# ProstheticController.net
KiCad netlist of a schematic drawn in Altium Designer
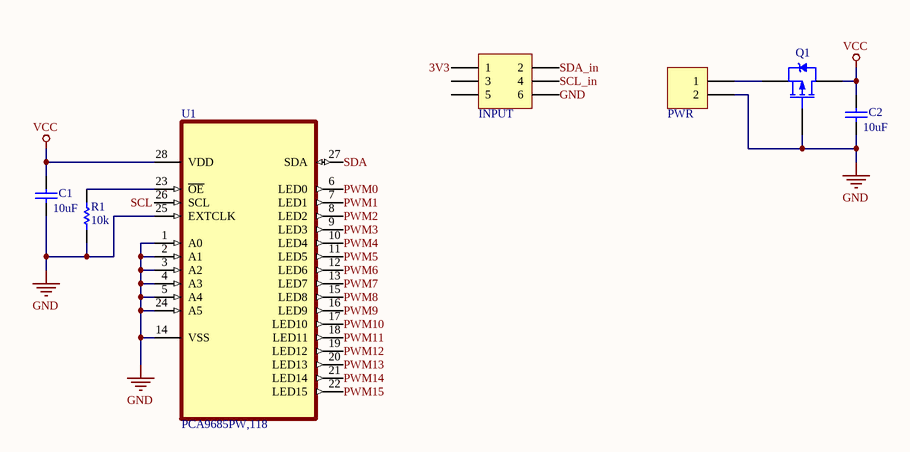
[diagram p0: ProstheticController.SchDoc]

(export (version "E")
  (design (tool "Eeschema 10.0.6"))
  (components
    (comp (ref "C1")
      (value "10uF")
      (footprint "0805")
      (description ".1, 10%, 50V")
      (fields (field (name "GFUPARTNO") "CL21A475KPFNNNE"))
      (libsource (lib "AltiumGFU64") (part "Cap"))
    )
    (comp (ref "C2")
      (value "10uF")
      (footprint "0805")
      (description ".1, 10%, 50V")
      (fields (field (name "GFUPARTNO") "CL21A475KPFNNNE"))
      (libsource (lib "AltiumGFU64") (part "Cap"))
    )
    (comp (ref "INPUT")
      (value "90131-0123")
      (footprint "HDR2X3")
      (description "MOLEX CONN HEADER 6POS 2ROW .100\" STR TIN")
      (libsource (lib "AltiumGFU64") (part "Header 3X2"))
    )
    (comp (ref "PWR")
      (value "90120-0122")
      (footprint "HDR1X2")
      (description "MOLEX CONN HEADER 2POS .100\" STR TIN")
      (libsource (lib "AltiumGFU64") (part "Header 2"))
    )
    (comp (ref "Q1")
      (value "FQP27P06")
      (footprint "TO-220")
      (description "MOSFET P-CH 60V 27A TO-220")
      (libsource (lib "AltiumGFU64") (part "MOSFET-P-ALT"))
    )
    (comp (ref "R1")
      (value "10k")
      (footprint "0805_RES_HD")
      (description "RES 10K OHM 1/8W 5% 0805")
      (fields (field (name "GFUPARTNO") "RC2012F752CS"))
      (libsource (lib "AltiumGFU64") (part "ResBasic"))
    )
    (comp (ref "U1")
      (value "PCA9685PW,118")
      (footprint "SnapEDApcb:SOP65P640X110-28N")
      (description "LED Driver IC 16 Output Linear PWM Dimming 25mA 28-TSSOP")
      (fields (field (name "DIGI-KEY_PART_NUMBER") "568-11925-1-ND") (field (name "MF") "NXP USA"))
      (libsource (lib "SERVO_DRIVER") (part "PCA9685PW,118"))
    )
  )
  (nets
    (net (code "1") (name "/3V3") (class "Default")
      (node (ref "INPUT") (pin "1") (pinfunction "1_1") (pintype "passive"))
    )
    (net (code "2") (name "/PWM0") (class "Default")
      (node (ref "U1") (pin "6") (pinfunction "LED0_6") (pintype "output"))
    )
    (net (code "3") (name "/PWM1") (class "Default")
      (node (ref "U1") (pin "7") (pinfunction "LED1_7") (pintype "output"))
    )
    (net (code "4") (name "/PWM2") (class "Default")
      (node (ref "U1") (pin "8") (pinfunction "LED2_8") (pintype "output"))
    )
    (net (code "5") (name "/PWM3") (class "Default")
      (node (ref "U1") (pin "9") (pinfunction "LED3_9") (pintype "output"))
    )
    (net (code "6") (name "/PWM4") (class "Default")
      (node (ref "U1") (pin "10") (pinfunction "LED4_10") (pintype "output"))
    )
    (net (code "7") (name "/PWM5") (class "Default")
      (node (ref "U1") (pin "11") (pinfunction "LED5_11") (pintype "output"))
    )
    (net (code "8") (name "/PWM6") (class "Default")
      (node (ref "U1") (pin "12") (pinfunction "LED6_12") (pintype "output"))
    )
    (net (code "9") (name "/PWM7") (class "Default")
      (node (ref "U1") (pin "13") (pinfunction "LED7_13") (pintype "output"))
    )
    (net (code "10") (name "/PWM8") (class "Default")
      (node (ref "U1") (pin "15") (pinfunction "LED8_15") (pintype "output"))
    )
    (net (code "11") (name "/PWM9") (class "Default")
      (node (ref "U1") (pin "16") (pinfunction "LED9_16") (pintype "output"))
    )
    (net (code "12") (name "/PWM10") (class "Default")
      (node (ref "U1") (pin "17") (pinfunction "LED10_17") (pintype "output"))
    )
    (net (code "13") (name "/PWM11") (class "Default")
      (node (ref "U1") (pin "18") (pinfunction "LED11_18") (pintype "output"))
    )
    (net (code "14") (name "/PWM12") (class "Default")
      (node (ref "U1") (pin "19") (pinfunction "LED12_19") (pintype "output"))
    )
    (net (code "15") (name "/PWM13") (class "Default")
      (node (ref "U1") (pin "20") (pinfunction "LED13_20") (pintype "output"))
    )
    (net (code "16") (name "/PWM14") (class "Default")
      (node (ref "U1") (pin "21") (pinfunction "LED14_21") (pintype "output"))
    )
    (net (code "17") (name "/PWM15") (class "Default")
      (node (ref "U1") (pin "22") (pinfunction "LED15_22") (pintype "output"))
    )
    (net (code "18") (name "/SCL") (class "Default")
      (node (ref "U1") (pin "26") (pinfunction "SCL_26") (pintype "input"))
    )
    (net (code "19") (name "/SCL_in") (class "Default")
      (node (ref "INPUT") (pin "4") (pinfunction "4_4") (pintype "passive"))
    )
    (net (code "20") (name "/SDA") (class "Default")
      (node (ref "U1") (pin "27") (pinfunction "SDA_27") (pintype "bidirectional"))
    )
    (net (code "21") (name "/SDA_in") (class "Default")
      (node (ref "INPUT") (pin "2") (pinfunction "2_2") (pintype "passive"))
    )
    (net (code "22") (name "GND") (class "Default")
      (node (ref "C1") (pin "1") (pinfunction "1_1") (pintype "passive"))
      (node (ref "C2") (pin "1") (pinfunction "1_1") (pintype "passive"))
      (node (ref "INPUT") (pin "6") (pinfunction "6_6") (pintype "passive"))
      (node (ref "PWR") (pin "2") (pinfunction "2_2") (pintype "passive"))
      (node (ref "Q1") (pin "1") (pinfunction "G_1") (pintype "passive"))
      (node (ref "R1") (pin "1") (pinfunction "1_1") (pintype "passive"))
      (node (ref "U1") (pin "1") (pinfunction "A0_1") (pintype "input"))
      (node (ref "U1") (pin "14") (pinfunction "VSS_14") (pintype "passive"))
      (node (ref "U1") (pin "2") (pinfunction "A1_2") (pintype "input"))
      (node (ref "U1") (pin "24") (pinfunction "A5_24") (pintype "input"))
      (node (ref "U1") (pin "25") (pinfunction "EXTCLK_25") (pintype "input"))
      (node (ref "U1") (pin "3") (pinfunction "A2_3") (pintype "input"))
      (node (ref "U1") (pin "4") (pinfunction "A3_4") (pintype "input"))
      (node (ref "U1") (pin "5") (pinfunction "A4_5") (pintype "input"))
    )
    (net (code "23") (name "Net-(Q1-S)") (class "Default")
      (node (ref "PWR") (pin "1") (pinfunction "1_1") (pintype "passive"))
      (node (ref "Q1") (pin "3") (pinfunction "S_3") (pintype "passive"))
    )
    (net (code "24") (name "Net-(U1-~{OE})") (class "Default")
      (node (ref "R1") (pin "2") (pinfunction "2_2") (pintype "passive"))
      (node (ref "U1") (pin "23") (pinfunction "~{OE}_23") (pintype "input"))
    )
    (net (code "25") (name "VCC") (class "Default")
      (node (ref "C1") (pin "2") (pinfunction "2_2") (pintype "passive"))
      (node (ref "C2") (pin "2") (pinfunction "2_2") (pintype "passive"))
      (node (ref "Q1") (pin "2") (pinfunction "D_2") (pintype "passive"))
      (node (ref "U1") (pin "28") (pinfunction "VDD_28") (pintype "power_in"))
    )
    (net (code "26") (name "unconnected-(INPUT-Pad3)") (class "Default")
      (node (ref "INPUT") (pin "3") (pinfunction "3_3") (pintype "passive"))
    )
    (net (code "27") (name "unconnected-(INPUT-Pad5)") (class "Default")
      (node (ref "INPUT") (pin "5") (pinfunction "5_5") (pintype "passive"))
    )
  )
)
